# 4_30.net
KiCad netlist of a schematic drawn in EasyEDA
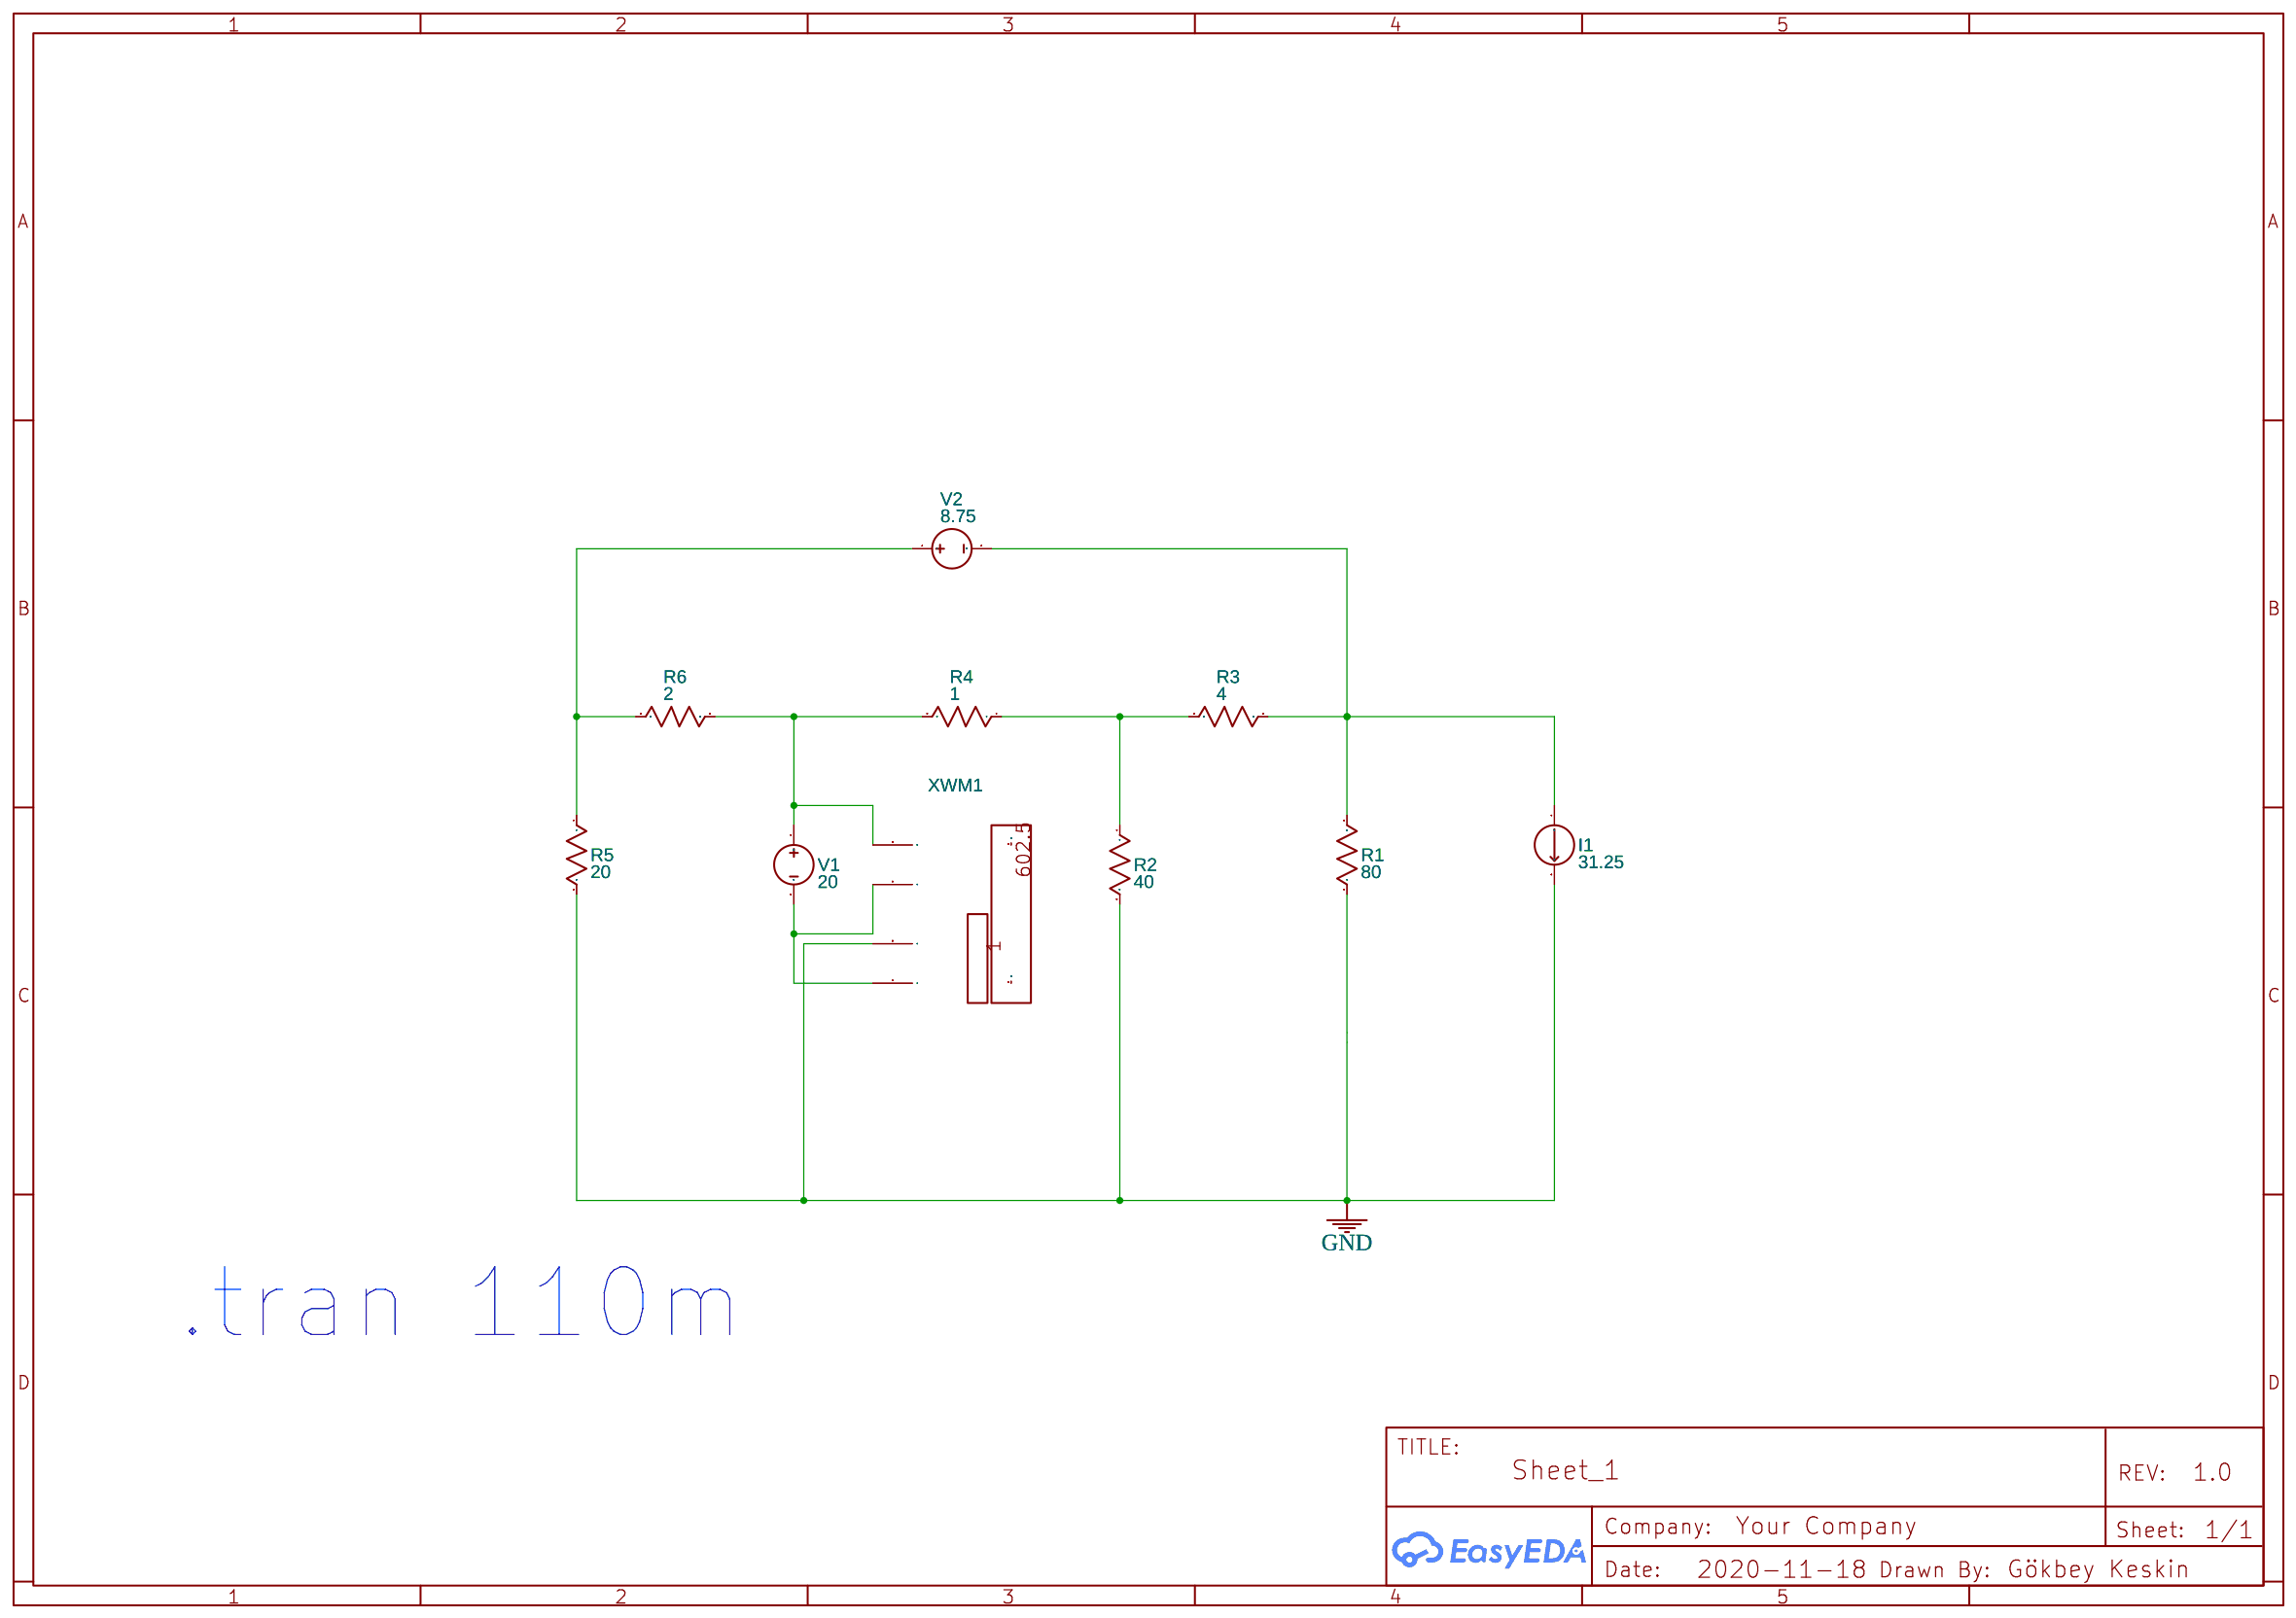
[diagram p0: schematic sheet]

(export (version "E")
  (design (tool "Eeschema 10.0.6"))
  (components
    (comp (ref "I1") (value "31.25") (libsource (lib "") (part "IDC")))
    (comp (ref "R1") (value "80") (libsource (lib "") (part "Resistor_US_2")))
    (comp (ref "R2") (value "40") (libsource (lib "") (part "Resistor_US_1")))
    (comp (ref "R3") (value "4") (libsource (lib "") (part "Resistor_US")))
    (comp (ref "R4") (value "1") (libsource (lib "") (part "Resistor_US")))
    (comp (ref "R5") (value "20") (libsource (lib "") (part "Resistor_US_1")))
    (comp (ref "R6") (value "2") (libsource (lib "") (part "Resistor_US_3")))
    (comp (ref "V1") (value "20") (libsource (lib "") (part "VDC")))
    (comp (ref "V2") (value "8.75") (libsource (lib "") (part "VDC_1")))
    (comp (ref "XWM1") (value "Wattmeter") (libsource (lib "") (part "WATTMETER")))
  )
  (nets
    (net (code "1") (name "GND") (class "Default")
      (node (ref "I1") (pin "2") (pinfunction "2_2") (pintype "unspecified"))
      (node (ref "R1") (pin "1") (pinfunction "1_1") (pintype "unspecified"))
      (node (ref "R2") (pin "2") (pinfunction "2_2") (pintype "unspecified"))
      (node (ref "R5") (pin "2") (pinfunction "2_2") (pintype "unspecified"))
      (node (ref "XWM1") (pin "3") (pinfunction "I+_3") (pintype "unspecified"))
    )
    (net (code "2") (name "Net-(I1-Pad1)") (class "Default")
      (node (ref "I1") (pin "1") (pinfunction "1_1") (pintype "unspecified"))
      (node (ref "R1") (pin "2") (pinfunction "2_2") (pintype "unspecified"))
      (node (ref "R3") (pin "1") (pinfunction "1_1") (pintype "unspecified"))
      (node (ref "V2") (pin "2") (pinfunction "2_2") (pintype "unspecified"))
    )
    (net (code "3") (name "Net-(R2-Pad1)") (class "Default")
      (node (ref "R2") (pin "1") (pinfunction "1_1") (pintype "unspecified"))
      (node (ref "R3") (pin "2") (pinfunction "2_2") (pintype "unspecified"))
      (node (ref "R4") (pin "1") (pinfunction "1_1") (pintype "unspecified"))
    )
    (net (code "4") (name "Net-(R5-Pad1)") (class "Default")
      (node (ref "R5") (pin "1") (pinfunction "1_1") (pintype "unspecified"))
      (node (ref "R6") (pin "1") (pinfunction "1_1") (pintype "unspecified"))
      (node (ref "V2") (pin "1") (pinfunction "1_1") (pintype "unspecified"))
    )
    (net (code "5") (name "Net-(XWM1-I-)") (class "Default")
      (node (ref "V1") (pin "2") (pinfunction "2_2") (pintype "unspecified"))
      (node (ref "XWM1") (pin "2") (pinfunction "V-_2") (pintype "unspecified"))
      (node (ref "XWM1") (pin "4") (pinfunction "I-_4") (pintype "unspecified"))
    )
    (net (code "6") (name "Net-(XWM1-V+)") (class "Default")
      (node (ref "R4") (pin "2") (pinfunction "2_2") (pintype "unspecified"))
      (node (ref "R6") (pin "2") (pinfunction "2_2") (pintype "unspecified"))
      (node (ref "V1") (pin "1") (pinfunction "1_1") (pintype "unspecified"))
      (node (ref "XWM1") (pin "1") (pinfunction "V+_1") (pintype "unspecified"))
    )
    (net (code "7") (name "unconnected-(XWM1-PadP)") (class "Default")
      (node (ref "XWM1") (pin "P") (pinfunction "P_P") (pintype "unspecified"))
    )
    (net (code "8") (name "unconnected-(XWM1-PadPF)") (class "Default")
      (node (ref "XWM1") (pin "PF") (pinfunction "PF_PF") (pintype "unspecified"))
    )
  )
)
